# Radio2_Aff.net
KiCad netlist of a schematic drawn in EAGLE
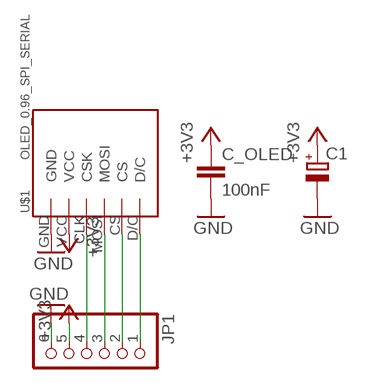
[diagram p0: schematic, sheet 1]

(export (version "E")
  (design (tool "Eeschema 10.0.6"))
  (components
    (comp (ref "C1")
      (value "CPOL-EUE2-5")
      (footprint "eagle-import:E2-5")
      (libsource (lib "eagle-import") (part "CPOL-EUE2-5"))
    )
    (comp (ref "C_OLED")
      (value "100nF")
      (footprint "eagle-import:C025-024X044")
      (libsource (lib "eagle-import") (part "C-EU025-024X044"))
    )
    (comp (ref "JP1")
      (value "PINHD-1X6")
      (footprint "eagle-import:1X06")
      (libsource (lib "eagle-import") (part "PINHD-1X6"))
    )
    (comp (ref "U$1")
      (value "OLED_0.96_SPI_SERIAL")
      (footprint "eagle-import:OLED_9.96_SPI_SERIAL")
      (libsource (lib "eagle-import") (part "OLED_0.96_SPI_SERIAL"))
    )
  )
  (nets
    (net (code "1") (name "+3V3") (class "Default")
      (node (ref "C1") (pin "+") (pinfunction "+_+") (pintype "passive"))
      (node (ref "C_OLED") (pin "1") (pinfunction "1_1") (pintype "passive"))
      (node (ref "JP1") (pin "5") (pinfunction "5_5") (pintype "passive"))
      (node (ref "U$1") (pin "VCC") (pinfunction "VCC_VCC") (pintype "bidirectional"))
    )
    (net (code "2") (name "GND") (class "Default")
      (node (ref "C1") (pin "-") (pinfunction "-_-") (pintype "passive"))
      (node (ref "C_OLED") (pin "2") (pinfunction "2_2") (pintype "passive"))
      (node (ref "JP1") (pin "6") (pinfunction "6_6") (pintype "passive"))
      (node (ref "U$1") (pin "GND") (pinfunction "GND_GND") (pintype "bidirectional"))
    )
    (net (code "3") (name "Net-(JP1-Pad1)") (class "Default")
      (node (ref "JP1") (pin "1") (pinfunction "1_1") (pintype "passive"))
      (node (ref "U$1") (pin "D/C") (pinfunction "D/C_D/C") (pintype "bidirectional"))
    )
    (net (code "4") (name "Net-(JP1-Pad2)") (class "Default")
      (node (ref "JP1") (pin "2") (pinfunction "2_2") (pintype "passive"))
      (node (ref "U$1") (pin "CS") (pinfunction "CS_CS") (pintype "bidirectional"))
    )
    (net (code "5") (name "Net-(JP1-Pad3)") (class "Default")
      (node (ref "JP1") (pin "3") (pinfunction "3_3") (pintype "passive"))
      (node (ref "U$1") (pin "MOSI") (pinfunction "MOSI_MOSI") (pintype "bidirectional"))
    )
    (net (code "6") (name "Net-(U$1-CSK)") (class "Default")
      (node (ref "JP1") (pin "4") (pinfunction "4_4") (pintype "passive"))
      (node (ref "U$1") (pin "CLK") (pinfunction "CSK_CLK") (pintype "bidirectional"))
    )
  )
)
